# ssChildSignalTower.net
KiCad netlist of a schematic drawn in EAGLE
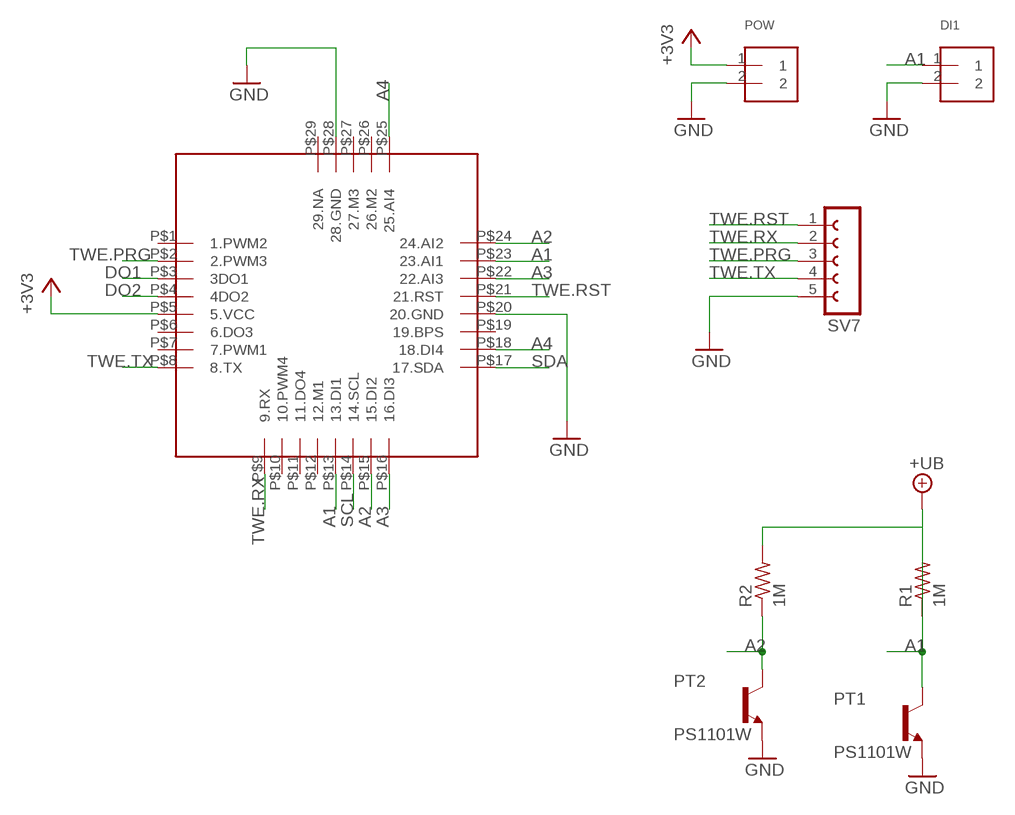
[diagram p0: schematic, sheet 1]

(export (version "E")
  (design (tool "Eeschema 10.0.6"))
  (components
    (comp (ref "DI1")
      (value "AMON0.5SQ_WIRE_HOLE")
      (footprint "eagle-import:AMON0.5SQ_WIRE_HOLE")
      (libsource (lib "eagle-import") (part "AMON0.5SQ_WIRE_HOLE"))
    )
    (comp (ref "POW")
      (value "AMON0.5SQ_WIRE_HOLE")
      (footprint "eagle-import:AMON0.5SQ_WIRE_HOLE")
      (libsource (lib "eagle-import") (part "AMON0.5SQ_WIRE_HOLE"))
    )
    (comp (ref "PT1")
      (value "PS1101W")
      (footprint "eagle-import:GL-01674-PS1101W-PHOTO-TRANSISTOR")
      (libsource (lib "eagle-import") (part "GL-01674-PS1101W-PHOTOTRANSISTOR"))
    )
    (comp (ref "PT2")
      (value "PS1101W")
      (footprint "eagle-import:GL-01674-PS1101W-PHOTO-TRANSISTOR")
      (libsource (lib "eagle-import") (part "GL-01674-PS1101W-PHOTOTRANSISTOR"))
    )
    (comp (ref "R1")
      (value "1M")
      (footprint "eagle-import:R0603")
      (libsource (lib "eagle-import") (part "R-US_R0603"))
    )
    (comp (ref "R2")
      (value "1M")
      (footprint "eagle-import:R0603")
      (libsource (lib "eagle-import") (part "R-US_R0603"))
    )
    (comp (ref "SV7")
      (value "FE05-1")
      (footprint "eagle-import:FE05-1")
      (libsource (lib "eagle-import") (part "FE05-1"))
    )
    (comp (ref "U$1")
      (value "LITE")
      (footprint "eagle-import:LITE")
      (libsource (lib "eagle-import") (part "LITE"))
    )
  )
  (nets
    (net (code "1") (name "+3V3") (class "Default")
      (node (ref "POW") (pin "1") (pinfunction "1_1") (pintype "bidirectional"))
      (node (ref "U$1") (pin "P$5") (pinfunction "5.VCC_P$5") (pintype "bidirectional"))
    )
    (net (code "2") (name "+UB") (class "Default")
      (node (ref "R1") (pin "1") (pinfunction "1_1") (pintype "passive"))
      (node (ref "R2") (pin "2") (pinfunction "2_2") (pintype "passive"))
    )
    (net (code "3") (name "/A1") (class "Default")
      (node (ref "DI1") (pin "1") (pinfunction "1_1") (pintype "bidirectional"))
      (node (ref "PT1") (pin "C") (pinfunction "C_C") (pintype "passive"))
      (node (ref "R1") (pin "2") (pinfunction "2_2") (pintype "passive"))
      (node (ref "U$1") (pin "P$13") (pinfunction "13.DI1_P$13") (pintype "bidirectional"))
      (node (ref "U$1") (pin "P$23") (pinfunction "23.AI1_P$23") (pintype "bidirectional"))
    )
    (net (code "4") (name "/A2") (class "Default")
      (node (ref "PT2") (pin "C") (pinfunction "C_C") (pintype "passive"))
      (node (ref "R2") (pin "1") (pinfunction "1_1") (pintype "passive"))
      (node (ref "U$1") (pin "P$15") (pinfunction "15.DI2_P$15") (pintype "bidirectional"))
      (node (ref "U$1") (pin "P$24") (pinfunction "24.AI2_P$24") (pintype "bidirectional"))
    )
    (net (code "5") (name "/A3") (class "Default")
      (node (ref "U$1") (pin "P$16") (pinfunction "16.DI3_P$16") (pintype "bidirectional"))
      (node (ref "U$1") (pin "P$22") (pinfunction "22.AI3_P$22") (pintype "bidirectional"))
    )
    (net (code "6") (name "/A4") (class "Default")
      (node (ref "U$1") (pin "P$18") (pinfunction "18.DI4_P$18") (pintype "bidirectional"))
      (node (ref "U$1") (pin "P$25") (pinfunction "25.AI4_P$25") (pintype "bidirectional"))
    )
    (net (code "7") (name "/DO1") (class "Default")
      (node (ref "U$1") (pin "P$3") (pinfunction "3DO1_P$3") (pintype "bidirectional"))
    )
    (net (code "8") (name "/DO2") (class "Default")
      (node (ref "U$1") (pin "P$4") (pinfunction "4DO2_P$4") (pintype "bidirectional"))
    )
    (net (code "9") (name "/SCL") (class "Default")
      (node (ref "U$1") (pin "P$14") (pinfunction "14.SCL_P$14") (pintype "bidirectional"))
    )
    (net (code "10") (name "/SDA") (class "Default")
      (node (ref "U$1") (pin "P$17") (pinfunction "17.SDA_P$17") (pintype "bidirectional"))
    )
    (net (code "11") (name "/TWE.PRG") (class "Default")
      (node (ref "SV7") (pin "3") (pinfunction "3_3") (pintype "passive"))
      (node (ref "U$1") (pin "P$2") (pinfunction "2.PWM3_P$2") (pintype "bidirectional"))
    )
    (net (code "12") (name "/TWE.RST") (class "Default")
      (node (ref "SV7") (pin "1") (pinfunction "1_1") (pintype "passive"))
      (node (ref "U$1") (pin "P$21") (pinfunction "21.RST_P$21") (pintype "bidirectional"))
    )
    (net (code "13") (name "/TWE.RX") (class "Default")
      (node (ref "SV7") (pin "2") (pinfunction "2_2") (pintype "passive"))
      (node (ref "U$1") (pin "P$9") (pinfunction "9.RX_P$9") (pintype "bidirectional"))
    )
    (net (code "14") (name "/TWE.TX") (class "Default")
      (node (ref "SV7") (pin "4") (pinfunction "4_4") (pintype "passive"))
      (node (ref "U$1") (pin "P$8") (pinfunction "8.TX_P$8") (pintype "bidirectional"))
    )
    (net (code "15") (name "GND") (class "Default")
      (node (ref "DI1") (pin "2") (pinfunction "2_2") (pintype "bidirectional"))
      (node (ref "POW") (pin "2") (pinfunction "2_2") (pintype "bidirectional"))
      (node (ref "PT1") (pin "E") (pinfunction "E_E") (pintype "passive"))
      (node (ref "PT2") (pin "E") (pinfunction "E_E") (pintype "passive"))
      (node (ref "SV7") (pin "5") (pinfunction "5_5") (pintype "passive"))
      (node (ref "U$1") (pin "P$20") (pinfunction "20.GND_P$20") (pintype "bidirectional"))
      (node (ref "U$1") (pin "P$28") (pinfunction "28.GND_P$28") (pintype "bidirectional"))
    )
    (net (code "16") (name "unconnected-(U$1-1.PWM2-PadP$1)") (class "Default")
      (node (ref "U$1") (pin "P$1") (pinfunction "1.PWM2_P$1") (pintype "bidirectional"))
    )
    (net (code "17") (name "unconnected-(U$1-6.DO3-PadP$6)") (class "Default")
      (node (ref "U$1") (pin "P$6") (pinfunction "6.DO3_P$6") (pintype "bidirectional"))
    )
    (net (code "18") (name "unconnected-(U$1-7.PWM1-PadP$7)") (class "Default")
      (node (ref "U$1") (pin "P$7") (pinfunction "7.PWM1_P$7") (pintype "bidirectional"))
    )
    (net (code "19") (name "unconnected-(U$1-10.PWM4-PadP$10)") (class "Default")
      (node (ref "U$1") (pin "P$10") (pinfunction "10.PWM4_P$10") (pintype "bidirectional"))
    )
    (net (code "20") (name "unconnected-(U$1-11.DO4-PadP$11)") (class "Default")
      (node (ref "U$1") (pin "P$11") (pinfunction "11.DO4_P$11") (pintype "bidirectional"))
    )
    (net (code "21") (name "unconnected-(U$1-12.M1-PadP$12)") (class "Default")
      (node (ref "U$1") (pin "P$12") (pinfunction "12.M1_P$12") (pintype "bidirectional"))
    )
    (net (code "22") (name "unconnected-(U$1-19.BPS-PadP$19)") (class "Default")
      (node (ref "U$1") (pin "P$19") (pinfunction "19.BPS_P$19") (pintype "bidirectional"))
    )
    (net (code "23") (name "unconnected-(U$1-26.M2-PadP$26)") (class "Default")
      (node (ref "U$1") (pin "P$26") (pinfunction "26.M2_P$26") (pintype "bidirectional"))
    )
    (net (code "24") (name "unconnected-(U$1-27.M3-PadP$27)") (class "Default")
      (node (ref "U$1") (pin "P$27") (pinfunction "27.M3_P$27") (pintype "bidirectional"))
    )
    (net (code "25") (name "unconnected-(U$1-29.NA-PadP$29)") (class "Default")
      (node (ref "U$1") (pin "P$29") (pinfunction "29.NA_P$29") (pintype "bidirectional"))
    )
  )
)
